# power_board1.net
KiCad netlist of a schematic drawn in Altium Designer
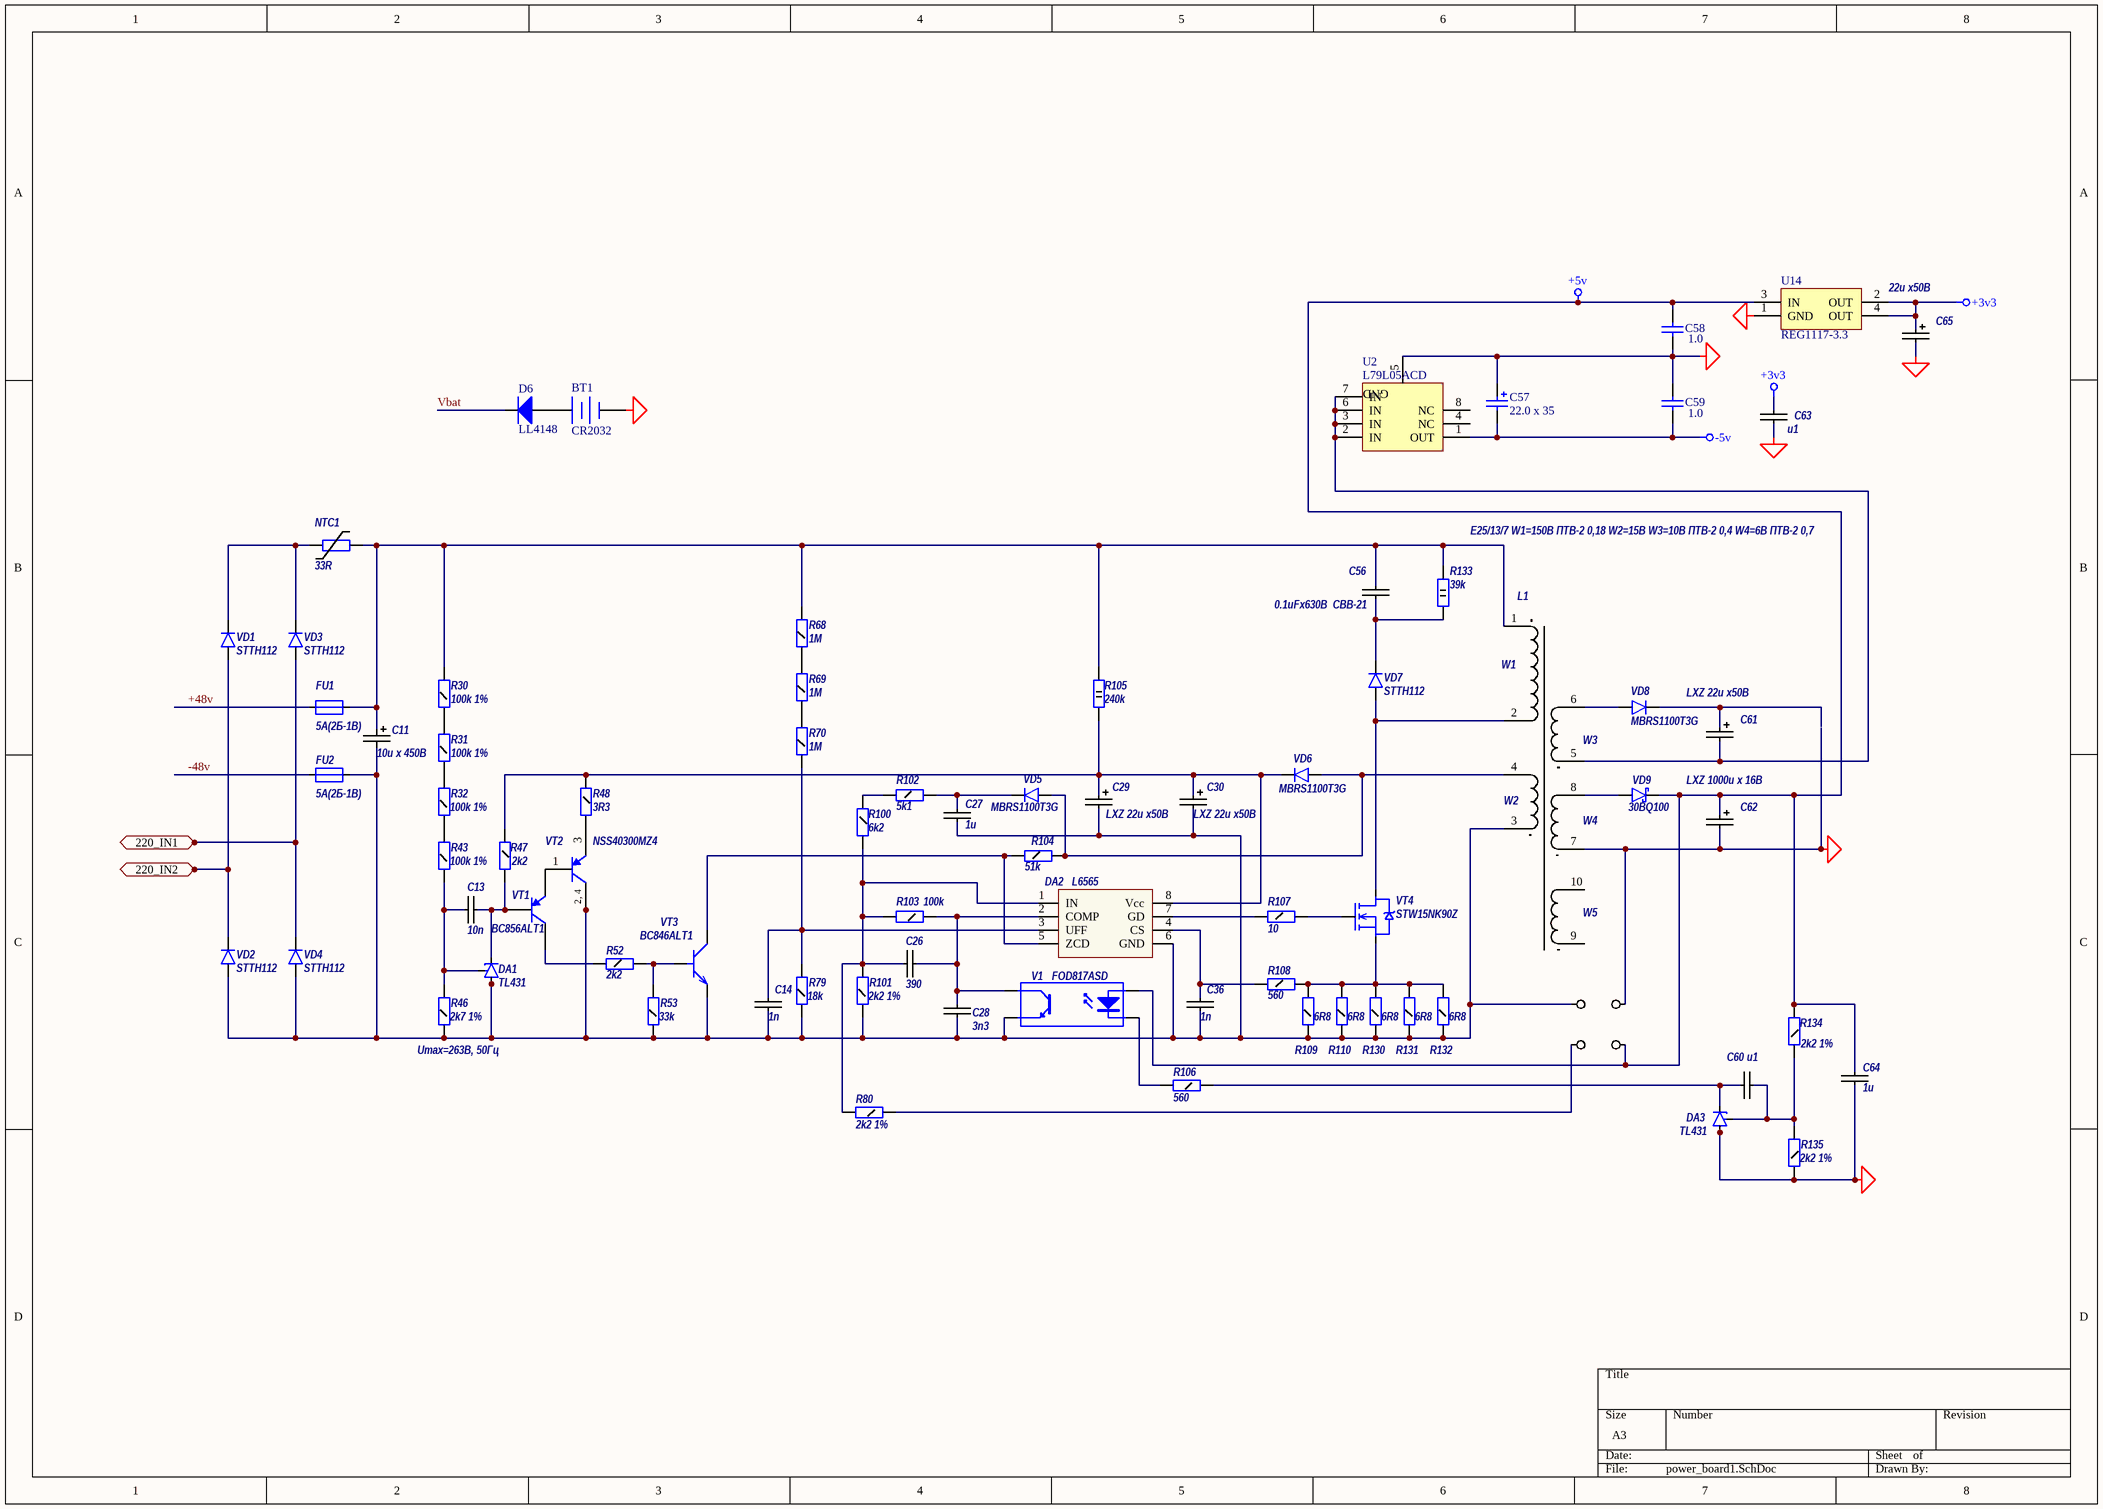
[diagram p0: power_board1.SchDoc]

(export (version "E")
  (design (tool "Eeschema 10.0.6"))
  (components
    (comp (ref "BT1")
      (value "CR2032")
      (footprint "BAT_SUPP")
      (description "Multicell Battery")
      (fields (field (name "MANUFACTURER") "Generic Components") (field (name "PUBLISHER") "Altium Limited"))
      (libsource (lib "Miscellaneous Devices") (part "Battery"))
    )
    (comp (ref "C11")
      (value "10u x 450B")
      (footprint "10uf x 450V")
      (fields (field (name "POWER") "450В"))
      (libsource (lib "Common") (part "10мкФ х 450В"))
    )
    (comp (ref "C13")
      (value "10n")
      (footprint "_1206")
      (fields
        (field (name "TOLERANCE") "10%")
        (field (name "MANUFACTURERPARTNUMBER") "CC1206 1мкФ±10% 50В X7R")
      )
      (libsource (lib "igorenja") (part "Capacitor"))
    )
    (comp (ref "C14")
      (value "1n")
      (footprint "_1206")
      (fields (field (name "TOLERANCE") "10%"))
      (libsource (lib "Common") (part "Capacitor"))
    )
    (comp (ref "C26")
      (value "390")
      (footprint "_1206")
      (fields (field (name "TOLERANCE") "10%"))
      (libsource (lib "Common") (part "Capacitor"))
    )
    (comp (ref "C27")
      (value "1u")
      (footprint "_1206")
      (fields (field (name "TOLERANCE") "10%"))
      (libsource (lib "Common") (part "Capacitor"))
    )
    (comp (ref "C28")
      (value "3n3")
      (footprint "_1206")
      (fields (field (name "TOLERANCE") "10%"))
      (libsource (lib "Common") (part "Capacitor"))
    )
    (comp (ref "C29")
      (value "LXZ 22u x50B")
      (footprint "CAP_POL_6.3x12")
      (fields (field (name "TOLERANCE") "20%") (field (name "MANUFACTURERPARTNUMBER") "22мкФ±20% 50В KMF"))
      (libsource (lib "igorenja") (part "CAP_POL"))
    )
    (comp (ref "C30")
      (value "LXZ 22u x50B")
      (footprint "CAP_POL_6.3x12")
      (fields (field (name "TOLERANCE") "20%") (field (name "MANUFACTURERPARTNUMBER") "22мкФ±20% 50В KMF"))
      (libsource (lib "igorenja") (part "CAP_POL"))
    )
    (comp (ref "C36")
      (value "1n")
      (footprint "_1206")
      (fields (field (name "TOLERANCE") "10%"))
      (libsource (lib "Common") (part "Capacitor"))
    )
    (comp (ref "C56")
      (value "0.1uFx630B  CBB-21")
      (footprint "0.1uf *630V")
      (fields (field (name "TOLERANCE") "20%") (field (name "MANUFACTURERPARTNUMBER") "0.1мкФ±20% 250В"))
      (libsource (lib "igorenja") (part "Capacitor"))
    )
    (comp (ref "C57")
      (value "22.0 x 35")
      (footprint "el3")
      (description "Polarized Capacitor (Radial)")
      (fields (field (name "MANUFACTURER") "Generic Components") (field (name "PUBLISHER") "Altium Limited"))
      (libsource (lib "PAL") (part "Cap Pol1"))
    )
    (comp (ref "C58")
      (value "1.0")
      (footprint "C3216-1206")
      (description "Capacitor (Semiconductor SIM Model)")
      (fields (field (name "MANUFACTURER") "Generic Components") (field (name "PUBLISHER") "Altium Limited"))
      (libsource (lib "Miscellaneous Devices") (part "Cap Semi"))
    )
    (comp (ref "C59")
      (value "1.0")
      (footprint "C3216-1206")
      (description "Capacitor (Semiconductor SIM Model)")
      (fields (field (name "MANUFACTURER") "Generic Components") (field (name "PUBLISHER") "Altium Limited"))
      (libsource (lib "Miscellaneous Devices") (part "Cap Semi"))
    )
    (comp (ref "C60")
      (value "u1")
      (footprint "_1206")
      (fields (field (name "TOLERANCE") "10%"))
      (libsource (lib "Common") (part "Capacitor"))
    )
    (comp (ref "C61")
      (value "LXZ 22u x50B")
      (footprint "CAP_POL_6.3x12")
      (fields (field (name "TOLERANCE") "20%") (field (name "MANUFACTURERPARTNUMBER") "22мкФ±20% 50В KMF"))
      (libsource (lib "igorenja") (part "CAP_POL"))
    )
    (comp (ref "C62")
      (value "LXZ 1000u x 16B")
      (footprint "CAP_POL_13x21")
      (description "1000 мкФ х 25В")
      (fields (field (name "TOLERANCE") "-20 +80%"))
      (libsource (lib "Common") (part "1000 мкФ х 25В"))
    )
    (comp (ref "C63")
      (value "u1")
      (footprint "_1206")
      (fields (field (name "TOLERANCE") "10%"))
      (libsource (lib "Common") (part "Capacitor"))
    )
    (comp (ref "C64")
      (value "1u")
      (footprint "_1206")
      (fields (field (name "TOLERANCE") "10%"))
      (libsource (lib "Common") (part "Capacitor"))
    )
    (comp (ref "C65")
      (value "22u x50B")
      (footprint "CAP_POL_6.3x12")
      (fields (field (name "TOLERANCE") "20%") (field (name "MANUFACTURERPARTNUMBER") "22мкФ±20% 50В KMF"))
      (libsource (lib "igorenja") (part "CAP_POL"))
    )
    (comp (ref "D6")
      (value "LL4148")
      (footprint "_1206d")
      (description "Default Diode")
      (fields (field (name "MANUFACTURER") "Generic Components") (field (name "PUBLISHER") "Altium Limited"))
      (libsource (lib "PAL") (part "Diode"))
    )
    (comp (ref "DA1") (value "TL431") (footprint "SO-G8") (libsource (lib "igorenja") (part "TL431")))
    (comp (ref "DA2") (value "L6565") (footprint "SO-G8") (libsource (lib "Common") (part "L6565")))
    (comp (ref "DA3") (value "TL431") (footprint "SO-G8") (libsource (lib "Common") (part "TL431")))
    (comp (ref "FU1") (value "5A(2Б-1В)") (footprint "FUSE-3A") (libsource (lib "igorenja") (part "FUSE")))
    (comp (ref "FU2") (value "5A(2Б-1В)") (footprint "FUSE-3A") (libsource (lib "igorenja") (part "FUSE")))
    (comp (ref "L1")
      (value "E25/13/7 W1=150B ПТВ-2 0,18 W2=15B W3=10B ПТВ-2 0,4 W4=6B ПТВ-2 0,7")
      (footprint "Lps_360RH")
      (description "Индуктивность")
      (libsource (lib "Common") (part "Lps_360RH"))
    )
    (comp (ref "NTC1")
      (value "33R")
      (footprint "NTC 33R")
      (description "Позистор")
      (libsource (lib "Common") (part "NTC 33R"))
    )
    (comp (ref "R30")
      (value "100k 1%")
      (footprint "_1206")
      (description "R1206")
      (fields (field (name "TOLERANCE") "5%"))
      (libsource (lib "") (part "R1206_1"))
    )
    (comp (ref "R31")
      (value "100k 1%")
      (footprint "_1206")
      (description "R1206")
      (fields (field (name "TOLERANCE") "5%"))
      (libsource (lib "") (part "R1206_1"))
    )
    (comp (ref "R32")
      (value "100k 1%")
      (footprint "_1206")
      (description "R1206")
      (fields (field (name "TOLERANCE") "1%"))
      (libsource (lib "") (part "R1206_1"))
    )
    (comp (ref "R43")
      (value "100k 1%")
      (footprint "_1206")
      (description "R1206")
      (fields (field (name "TOLERANCE") "1%"))
      (libsource (lib "") (part "R1206_1"))
    )
    (comp (ref "R46")
      (value "2k7 1%")
      (footprint "_1206")
      (description "R1206")
      (fields (field (name "TOLERANCE") "1%"))
      (libsource (lib "") (part "R1206_1"))
    )
    (comp (ref "R47")
      (value "2k2")
      (footprint "_1206")
      (description "R1206")
      (fields (field (name "TOLERANCE") "1%"))
      (libsource (lib "Common") (part "R1206"))
    )
    (comp (ref "R48")
      (value "3R3")
      (footprint "_1206")
      (description "R1206")
      (fields (field (name "TOLERANCE") "1%"))
      (libsource (lib "Common") (part "R1206"))
    )
    (comp (ref "R52")
      (value "2k2")
      (footprint "_1206")
      (description "R1206")
      (fields (field (name "TOLERANCE") "1%"))
      (libsource (lib "") (part "R1206_2"))
    )
    (comp (ref "R53")
      (value "33k")
      (footprint "_1206")
      (description "R1206")
      (fields (field (name "TOLERANCE") "1%"))
      (libsource (lib "") (part "R1206_1"))
    )
    (comp (ref "R68")
      (value "1M")
      (footprint "_1206")
      (description "R1206")
      (fields (field (name "TOLERANCE") "5%"))
      (libsource (lib "") (part "R1206_1"))
    )
    (comp (ref "R69")
      (value "1M")
      (footprint "_1206")
      (description "R1206")
      (fields (field (name "TOLERANCE") "5%"))
      (libsource (lib "") (part "R1206_1"))
    )
    (comp (ref "R70")
      (value "1M")
      (footprint "_1206")
      (description "R1206")
      (fields (field (name "TOLERANCE") "1%"))
      (libsource (lib "") (part "R1206_1"))
    )
    (comp (ref "R79")
      (value "18k")
      (footprint "_1206")
      (description "R1206")
      (fields (field (name "TOLERANCE") "1%"))
      (libsource (lib "") (part "R1206_1"))
    )
    (comp (ref "R80")
      (value "2k2 1%")
      (footprint "_1206")
      (description "R1206")
      (fields (field (name "TOLERANCE") "1%"))
      (libsource (lib "") (part "R1206_3"))
    )
    (comp (ref "R100")
      (value "6k2")
      (footprint "_1206")
      (description "R1206")
      (fields (field (name "TOLERANCE") "1%"))
      (libsource (lib "Common") (part "R1206"))
    )
    (comp (ref "R101")
      (value "2k2 1%")
      (footprint "_1206")
      (description "R1206")
      (fields (field (name "TOLERANCE") "1%"))
      (libsource (lib "") (part "R1206_1"))
    )
    (comp (ref "R102")
      (value "5k1")
      (footprint "_1206")
      (description "R1206")
      (fields (field (name "TOLERANCE") "1%"))
      (libsource (lib "") (part "R1206_2"))
    )
    (comp (ref "R103")
      (value "100k")
      (footprint "_1206")
      (description "R1206")
      (fields (field (name "TOLERANCE") "1%"))
      (libsource (lib "") (part "R1206_3"))
    )
    (comp (ref "R104")
      (value "51k")
      (footprint "_1206")
      (description "R1206")
      (fields (field (name "TOLERANCE") "5%"))
      (libsource (lib "") (part "R1206_2"))
    )
    (comp (ref "R105")
      (value "240k")
      (footprint "MF-2 vert")
      (fields (field (name "TOLERANCE") "10%"))
      (libsource (lib "Common") (part "Res 2W"))
    )
    (comp (ref "R106")
      (value "560")
      (footprint "_1206")
      (description "R1206")
      (fields (field (name "TOLERANCE") "1%"))
      (libsource (lib "") (part "R1206_3"))
    )
    (comp (ref "R107")
      (value "10")
      (footprint "_1206")
      (description "R1206")
      (fields (field (name "TOLERANCE") "5%"))
      (libsource (lib "") (part "R1206_2"))
    )
    (comp (ref "R108")
      (value "560")
      (footprint "_1206")
      (description "R1206")
      (fields (field (name "TOLERANCE") "5%"))
      (libsource (lib "") (part "R1206_2"))
    )
    (comp (ref "R109")
      (value "6R8")
      (footprint "_1206")
      (description "R1206")
      (fields (field (name "TOLERANCE") "5%"))
      (libsource (lib "") (part "R1206_1"))
    )
    (comp (ref "R110")
      (value "6R8")
      (footprint "_1206")
      (description "R1206")
      (fields (field (name "TOLERANCE") "5%"))
      (libsource (lib "") (part "R1206_1"))
    )
    (comp (ref "R130")
      (value "6R8")
      (footprint "_1206")
      (description "R1206")
      (fields (field (name "TOLERANCE") "5%"))
      (libsource (lib "") (part "R1206_1"))
    )
    (comp (ref "R131")
      (value "6R8")
      (footprint "_1206")
      (description "R1206")
      (fields (field (name "TOLERANCE") "5%"))
      (libsource (lib "") (part "R1206_1"))
    )
    (comp (ref "R132")
      (value "6R8")
      (footprint "_1206")
      (description "R1206")
      (fields (field (name "TOLERANCE") "5%"))
      (libsource (lib "") (part "R1206_1"))
    )
    (comp (ref "R133") (value "39k") (footprint "Res 2W") (libsource (lib "Common") (part "Res 2W")))
    (comp (ref "R134")
      (value "2k2 1%")
      (footprint "_1206")
      (description "R1206")
      (fields (field (name "TOLERANCE") "1%"))
      (libsource (lib "") (part "R1206_2"))
    )
    (comp (ref "R135")
      (value "2k2 1%")
      (footprint "_1206")
      (description "R1206")
      (fields (field (name "TOLERANCE") "1%"))
      (libsource (lib "") (part "R1206_2"))
    )
    (comp (ref "U2")
      (value "L79L05ACD")
      (footprint "SO-G8")
      (description "Negative Voltage Regulator")
      (fields (field (name "MANUFACTURER") "ST-Microelectronics") (field (name "PUBLISHER") "Altium Limited"))
      (libsource (lib "ST Power Mgt Voltage Regulator") (part "L79L05ACD"))
    )
    (comp (ref "U14")
      (value "REG1117-3.3")
      (footprint "SIP-G3/C7.4")
      (description "800mA and 1A Low Dropout Positive Regulator 2.85V, 3.3V, 5V, and Adjustable")
      (fields (field (name "MANUFACTURER") "Burr-Brown") (field (name "PUBLISHER") "Altium Limited"))
      (libsource (lib "BB Power Mgt Voltage Regulator") (part "REG1117-3.3"))
    )
    (comp (ref "V1")
      (value "FOD817ASD")
      (footprint "FOD817ASD")
      (libsource (lib "Common") (part "FOD817ASD"))
    )
    (comp (ref "VD1")
      (value "STTH112")
      (footprint "10bq*")
      (fields (field (name "MANUFACTURERPARTNUMBER") "STTH2R060U"))
      (libsource (lib "IVERTORSICH") (part "DIOD_2"))
    )
    (comp (ref "VD2")
      (value "STTH112")
      (footprint "10bq*")
      (fields (field (name "MANUFACTURERPARTNUMBER") "STTH2R060U"))
      (libsource (lib "IVERTORSICH") (part "DIOD_2"))
    )
    (comp (ref "VD3")
      (value "STTH112")
      (footprint "10bq*")
      (fields (field (name "MANUFACTURERPARTNUMBER") "STTH2R060U"))
      (libsource (lib "IVERTORSICH") (part "DIOD_2"))
    )
    (comp (ref "VD4")
      (value "STTH112")
      (footprint "10bq*")
      (fields (field (name "MANUFACTURERPARTNUMBER") "STTH2R060U"))
      (libsource (lib "IVERTORSICH") (part "DIOD_2"))
    )
    (comp (ref "VD5") (value "MBRS1100T3G") (footprint "10bq*") (libsource (lib "Common") (part "DIOD_1")))
    (comp (ref "VD6") (value "MBRS1100T3G") (footprint "10bq*") (libsource (lib "Common") (part "DIOD_1")))
    (comp (ref "VD7")
      (value "STTH112")
      (footprint "10bq*")
      (fields (field (name "MANUFACTURERPARTNUMBER") "STTH2R060U"))
      (libsource (lib "IVERTORSICH") (part "DIOD_2"))
    )
    (comp (ref "VD8") (value "MBRS1100T3G") (footprint "10bq*") (libsource (lib "Common") (part "DIOD_1")))
    (comp (ref "VD9") (value "30BQ100") (footprint "30bq*") (libsource (lib "igorenja") (part "DIOD_SH")))
    (comp (ref "VT1")
      (value "BC856ALT1")
      (footprint "318-08")
      (description "General Purpose Transistor PNP Silicon")
      (fields (field (name "MANUFACTURER") "ON Semiconductor") (field (name "PUBLISHER") "Altium Limited"))
      (libsource (lib "Common") (part "BC856ALT1"))
    )
    (comp (ref "VT2")
      (value "NSS40300MZ4")
      (footprint "SOT223_N")
      (description "Транзистор")
      (fields (field (name "PUBLISHER") "Altium Limited"))
      (libsource (lib "Philips Discrete BJT - Medium Power") (part "BSP32"))
    )
    (comp (ref "VT3")
      (value "BC846ALT1")
      (footprint "SOT-23")
      (libsource (lib "igorenja") (part "TRANS_npn"))
    )
    (comp (ref "VT4")
      (value "STW15NK90Z")
      (footprint "IRFP4468_BS")
      (fields (field (name "MANUFACTURER") "International Rectifier"))
      (libsource (lib "Common") (part "irfp4468_otv"))
    )
    (comp (ref "XP1") (value "PAD") (footprint "PAD_otv") (libsource (lib "Common") (part "PAD")))
    (comp (ref "XP2") (value "PAD") (footprint "PAD_otv") (libsource (lib "Common") (part "PAD")))
    (comp (ref "XP3") (value "PAD") (footprint "PAD_otv") (libsource (lib "Common") (part "PAD")))
    (comp (ref "XP4") (value "PAD") (footprint "PAD_otv") (libsource (lib "Common") (part "PAD")))
    (comp (ref "XP5") (value "PAD") (footprint "PAD_otv") (libsource (lib "Common") (part "PAD")))
    (comp (ref "XP6") (value "PAD") (footprint "PAD_otv") (libsource (lib "Common") (part "PAD")))
  )
  (nets
    (net (code "1") (name "+3v3") (class "Default")
      (node (ref "C63") (pin "1") (pinfunction "OA_1") (pintype "passive"))
      (node (ref "C65") (pin "+") (pintype "passive"))
      (node (ref "U14") (pin "2") (pinfunction "OUT_2") (pintype "power_in"))
      (node (ref "U14") (pin "4") (pinfunction "OUT_4") (pintype "power_in"))
    )
    (net (code "2") (name "+5v") (class "Default")
      (node (ref "C58") (pin "2") (pinfunction "2_2") (pintype "passive"))
      (node (ref "C62") (pin "+") (pintype "passive"))
      (node (ref "C64") (pin "1") (pinfunction "OA_1") (pintype "passive"))
      (node (ref "R134") (pin "2") (pinfunction "2_2") (pintype "passive"))
      (node (ref "U14") (pin "3") (pinfunction "IN_3") (pintype "power_in"))
      (node (ref "V1") (pin "1") (pinfunction "A_1") (pintype "passive"))
      (node (ref "VD9") (pin "2") (pintype "passive"))
      (node (ref "XP6") (pin "1") (pintype "passive"))
    )
    (net (code "3") (name "-5v") (class "Default")
      (node (ref "C57") (pin "2") (pinfunction "2_2") (pintype "passive"))
      (node (ref "C59") (pin "1") (pinfunction "1_1") (pintype "passive"))
      (node (ref "U2") (pin "1") (pinfunction "OUT_1") (pintype "power_in"))
    )
    (net (code "4") (name "/+48v") (class "Default")
      (node (ref "FU1") (pin "1") (pinfunction "0_1") (pintype "passive"))
    )
    (net (code "5") (name "/-48v") (class "Default")
      (node (ref "FU2") (pin "1") (pinfunction "0_1") (pintype "passive"))
    )
    (net (code "6") (name "/220_IN1") (class "Default")
      (node (ref "VD3") (pin "1") (pintype "passive"))
      (node (ref "VD4") (pin "2") (pintype "passive"))
      (node (ref "XP1") (pin "1") (pintype "passive"))
    )
    (net (code "7") (name "/220_IN2") (class "Default")
      (node (ref "VD1") (pin "1") (pintype "passive"))
      (node (ref "VD2") (pin "2") (pintype "passive"))
      (node (ref "XP2") (pin "1") (pintype "passive"))
    )
    (net (code "8") (name "/Vbat") (class "Default")
      (node (ref "D6") (pin "2") (pinfunction "K_2") (pintype "passive"))
    )
    (net (code "9") (name "GND") (class "Default")
      (node (ref "BT1") (pin "2") (pinfunction "-_2") (pintype "passive"))
      (node (ref "C57") (pin "1") (pinfunction "1_1") (pintype "passive"))
      (node (ref "C58") (pin "1") (pinfunction "1_1") (pintype "passive"))
      (node (ref "C59") (pin "2") (pinfunction "2_2") (pintype "passive"))
      (node (ref "C62") (pin "-") (pintype "passive"))
      (node (ref "C63") (pin "2") (pinfunction "OA_2") (pintype "passive"))
      (node (ref "C64") (pin "2") (pinfunction "OA_2") (pintype "passive"))
      (node (ref "C65") (pin "-") (pintype "passive"))
      (node (ref "DA3") (pin "6") (pintype "passive"))
      (node (ref "DA3") (pin "7") (pintype "passive"))
      (node (ref "L1") (pin "7") (pintype "passive"))
      (node (ref "R135") (pin "1") (pinfunction "1_1") (pintype "passive"))
      (node (ref "U14") (pin "1") (pinfunction "GND_1") (pintype "power_in"))
      (node (ref "U2") (pin "5") (pinfunction "GND_5") (pintype "power_in"))
      (node (ref "XP5") (pin "1") (pintype "passive"))
    )
    (net (code "10") (name "Net-(BT1-+)") (class "Default")
      (node (ref "BT1") (pin "1") (pinfunction "+_1") (pintype "passive"))
      (node (ref "D6") (pin "1") (pinfunction "A_1") (pintype "passive"))
    )
    (net (code "11") (name "Net-(C13-OA-Pad1)") (class "Default")
      (node (ref "C13") (pin "1") (pinfunction "OA_1") (pintype "passive"))
      (node (ref "DA1") (pin "8") (pintype "passive"))
      (node (ref "R43") (pin "1") (pinfunction "1_1") (pintype "passive"))
      (node (ref "R46") (pin "2") (pinfunction "2_2") (pintype "passive"))
    )
    (net (code "12") (name "Net-(C27-OA-Pad1)") (class "Default")
      (node (ref "C27") (pin "1") (pinfunction "OA_1") (pintype "passive"))
      (node (ref "R102") (pin "2") (pinfunction "2_2") (pintype "passive"))
      (node (ref "VD5") (pin "2") (pintype "passive"))
    )
    (net (code "13") (name "Net-(C56-OA-Pad2)") (class "Default")
      (node (ref "C56") (pin "2") (pinfunction "OA_2") (pintype "passive"))
      (node (ref "R133") (pin "1") (pinfunction "1_1") (pintype "passive"))
      (node (ref "VD7") (pin "2") (pintype "passive"))
    )
    (net (code "14") (name "Net-(C60-OA-Pad1)") (class "Default")
      (node (ref "C60") (pin "1") (pinfunction "OA_1") (pintype "passive"))
      (node (ref "DA3") (pin "1") (pintype "passive"))
      (node (ref "R106") (pin "1") (pinfunction "1_1") (pintype "passive"))
    )
    (net (code "15") (name "Net-(C60-OA-Pad2)") (class "Default")
      (node (ref "C60") (pin "2") (pinfunction "OA_2") (pintype "passive"))
      (node (ref "DA3") (pin "8") (pintype "passive"))
      (node (ref "R134") (pin "1") (pinfunction "1_1") (pintype "passive"))
      (node (ref "R135") (pin "2") (pinfunction "2_2") (pintype "passive"))
    )
    (net (code "16") (name "Net-(C61-Pad+)") (class "Default")
      (node (ref "C61") (pin "+") (pintype "passive"))
      (node (ref "VD8") (pin "2") (pintype "passive"))
    )
    (net (code "17") (name "Net-(C61-Pad-)") (class "Default")
      (node (ref "C61") (pin "-") (pintype "passive"))
      (node (ref "L1") (pin "5") (pintype "passive"))
      (node (ref "U2") (pin "2") (pinfunction "IN_2") (pintype "power_in"))
      (node (ref "U2") (pin "3") (pinfunction "IN_3") (pintype "power_in"))
      (node (ref "U2") (pin "6") (pinfunction "IN_6") (pintype "power_in"))
      (node (ref "U2") (pin "7") (pinfunction "IN_7") (pintype "power_in"))
    )
    (net (code "18") (name "Net-(DA2-COMP)") (class "Default")
      (node (ref "C26") (pin "2") (pinfunction "OA_2") (pintype "passive"))
      (node (ref "C28") (pin "2") (pinfunction "OA_2") (pintype "passive"))
      (node (ref "DA2") (pin "2") (pinfunction "COMP_2") (pintype "passive"))
      (node (ref "R103") (pin "1") (pinfunction "1_1") (pintype "passive"))
      (node (ref "V1") (pin "4") (pinfunction "C_4") (pintype "passive"))
    )
    (net (code "19") (name "Net-(DA2-CS)") (class "Default")
      (node (ref "C36") (pin "1") (pinfunction "OA_1") (pintype "passive"))
      (node (ref "DA2") (pin "4") (pinfunction "CS_4") (pintype "passive"))
      (node (ref "R108") (pin "1") (pinfunction "1_1") (pintype "passive"))
    )
    (net (code "20") (name "Net-(DA2-GD)") (class "Default")
      (node (ref "DA2") (pin "7") (pinfunction "GD_7") (pintype "passive"))
      (node (ref "R107") (pin "1") (pinfunction "1_1") (pintype "passive"))
    )
    (net (code "21") (name "Net-(DA2-GND)") (class "Default")
      (node (ref "C11") (pin "2") (pintype "passive"))
      (node (ref "C14") (pin "2") (pinfunction "OA_2") (pintype "passive"))
      (node (ref "C27") (pin "2") (pinfunction "OA_2") (pintype "passive"))
      (node (ref "C28") (pin "1") (pinfunction "OA_1") (pintype "passive"))
      (node (ref "C29") (pin "-") (pintype "passive"))
      (node (ref "C30") (pin "-") (pintype "passive"))
      (node (ref "C36") (pin "2") (pinfunction "OA_2") (pintype "passive"))
      (node (ref "DA1") (pin "6") (pintype "passive"))
      (node (ref "DA1") (pin "7") (pintype "passive"))
      (node (ref "DA2") (pin "6") (pinfunction "GND_6") (pintype "passive"))
      (node (ref "FU2") (pin "2") (pinfunction "1_2") (pintype "passive"))
      (node (ref "L1") (pin "3") (pintype "passive"))
      (node (ref "R101") (pin "1") (pinfunction "1_1") (pintype "passive"))
      (node (ref "R109") (pin "1") (pinfunction "1_1") (pintype "passive"))
      (node (ref "R110") (pin "1") (pinfunction "1_1") (pintype "passive"))
      (node (ref "R130") (pin "1") (pinfunction "1_1") (pintype "passive"))
      (node (ref "R131") (pin "1") (pinfunction "1_1") (pintype "passive"))
      (node (ref "R132") (pin "1") (pinfunction "1_1") (pintype "passive"))
      (node (ref "R46") (pin "1") (pinfunction "1_1") (pintype "passive"))
      (node (ref "R53") (pin "1") (pinfunction "1_1") (pintype "passive"))
      (node (ref "R79") (pin "1") (pinfunction "1_1") (pintype "passive"))
      (node (ref "V1") (pin "3") (pinfunction "E_3") (pintype "passive"))
      (node (ref "VD2") (pin "1") (pintype "passive"))
      (node (ref "VD4") (pin "1") (pintype "passive"))
      (node (ref "VT2") (pin "2") (pinfunction "C_2") (pintype "passive"))
      (node (ref "VT2") (pin "4") (pinfunction "C_4") (pintype "passive"))
      (node (ref "VT3") (pin "2") (pintype "passive"))
      (node (ref "XP3") (pin "1") (pintype "passive"))
    )
    (net (code "22") (name "Net-(DA2-IN)") (class "Default")
      (node (ref "C26") (pin "1") (pinfunction "OA_1") (pintype "passive"))
      (node (ref "DA2") (pin "1") (pinfunction "IN_1") (pintype "passive"))
      (node (ref "R100") (pin "2") (pinfunction "2_2") (pintype "passive"))
      (node (ref "R101") (pin "2") (pinfunction "2_2") (pintype "passive"))
      (node (ref "R103") (pin "2") (pinfunction "2_2") (pintype "passive"))
      (node (ref "R80") (pin "2") (pinfunction "2_2") (pintype "passive"))
    )
    (net (code "23") (name "Net-(DA2-UFF)") (class "Default")
      (node (ref "C14") (pin "1") (pinfunction "OA_1") (pintype "passive"))
      (node (ref "DA2") (pin "3") (pinfunction "UFF_3") (pintype "passive"))
      (node (ref "R70") (pin "1") (pinfunction "1_1") (pintype "passive"))
      (node (ref "R79") (pin "2") (pinfunction "2_2") (pintype "passive"))
    )
    (net (code "24") (name "Net-(DA2-Vcc)") (class "Default")
      (node (ref "C29") (pin "+") (pintype "passive"))
      (node (ref "C30") (pin "+") (pintype "passive"))
      (node (ref "DA2") (pin "8") (pinfunction "Vcc_8") (pintype "passive"))
      (node (ref "R105") (pin "1") (pinfunction "1_1") (pintype "passive"))
      (node (ref "R47") (pin "1") (pinfunction "1_1") (pintype "passive"))
      (node (ref "R48") (pin "1") (pinfunction "1_1") (pintype "passive"))
      (node (ref "VD6") (pin "2") (pintype "passive"))
    )
    (net (code "25") (name "Net-(DA2-ZCD)") (class "Default")
      (node (ref "DA2") (pin "5") (pinfunction "ZCD_5") (pintype "passive"))
      (node (ref "R104") (pin "1") (pinfunction "1_1") (pintype "passive"))
      (node (ref "VT3") (pin "3") (pintype "passive"))
    )
    (net (code "26") (name "Net-(FU1-1)") (class "Default")
      (node (ref "C11") (pin "1") (pintype "passive"))
      (node (ref "C56") (pin "1") (pinfunction "OA_1") (pintype "passive"))
      (node (ref "FU1") (pin "2") (pinfunction "1_2") (pintype "passive"))
      (node (ref "L1") (pin "1") (pintype "passive"))
      (node (ref "NTC1") (pin "2") (pinfunction "2_2") (pintype "passive"))
      (node (ref "R105") (pin "2") (pinfunction "2_2") (pintype "passive"))
      (node (ref "R133") (pin "2") (pinfunction "2_2") (pintype "passive"))
      (node (ref "R30") (pin "2") (pinfunction "2_2") (pintype "passive"))
      (node (ref "R68") (pin "2") (pinfunction "2_2") (pintype "passive"))
    )
    (net (code "27") (name "Net-(L1-Pad4)") (class "Default")
      (node (ref "L1") (pin "4") (pintype "passive"))
      (node (ref "R104") (pin "2") (pinfunction "2_2") (pintype "passive"))
      (node (ref "VD5") (pin "1") (pintype "passive"))
      (node (ref "VD6") (pin "1") (pintype "passive"))
    )
    (net (code "28") (name "Net-(L1-Pad6)") (class "Default")
      (node (ref "L1") (pin "6") (pintype "passive"))
      (node (ref "VD8") (pin "1") (pintype "passive"))
    )
    (net (code "29") (name "Net-(L1-Pad8)") (class "Default")
      (node (ref "L1") (pin "8") (pintype "passive"))
      (node (ref "VD9") (pin "1") (pintype "passive"))
    )
    (net (code "30") (name "Net-(NTC1-Pad1)") (class "Default")
      (node (ref "NTC1") (pin "1") (pinfunction "1_1") (pintype "passive"))
      (node (ref "VD1") (pin "2") (pintype "passive"))
      (node (ref "VD3") (pin "2") (pintype "passive"))
    )
    (net (code "31") (name "Net-(R30-Pad1)") (class "Default")
      (node (ref "R30") (pin "1") (pinfunction "1_1") (pintype "passive"))
      (node (ref "R31") (pin "2") (pinfunction "2_2") (pintype "passive"))
    )
    (net (code "32") (name "Net-(R31-Pad1)") (class "Default")
      (node (ref "R31") (pin "1") (pinfunction "1_1") (pintype "passive"))
      (node (ref "R32") (pin "2") (pinfunction "2_2") (pintype "passive"))
    )
    (net (code "33") (name "Net-(R32-Pad1)") (class "Default")
      (node (ref "R32") (pin "1") (pinfunction "1_1") (pintype "passive"))
      (node (ref "R43") (pin "2") (pinfunction "2_2") (pintype "passive"))
    )
    (net (code "34") (name "Net-(R52-Pad2)") (class "Default")
      (node (ref "R52") (pin "2") (pinfunction "2_2") (pintype "passive"))
      (node (ref "R53") (pin "2") (pinfunction "2_2") (pintype "passive"))
      (node (ref "VT3") (pin "1") (pintype "passive"))
    )
    (net (code "35") (name "Net-(R68-Pad1)") (class "Default")
      (node (ref "R68") (pin "1") (pinfunction "1_1") (pintype "passive"))
      (node (ref "R69") (pin "2") (pinfunction "2_2") (pintype "passive"))
    )
    (net (code "36") (name "Net-(R69-Pad1)") (class "Default")
      (node (ref "R69") (pin "1") (pinfunction "1_1") (pintype "passive"))
      (node (ref "R70") (pin "2") (pinfunction "2_2") (pintype "passive"))
    )
    (net (code "37") (name "Net-(R80-Pad1)") (class "Default")
      (node (ref "R80") (pin "1") (pinfunction "1_1") (pintype "passive"))
      (node (ref "XP4") (pin "1") (pintype "passive"))
    )
    (net (code "38") (name "Net-(R100-Pad1)") (class "Default")
      (node (ref "R100") (pin "1") (pinfunction "1_1") (pintype "passive"))
      (node (ref "R102") (pin "1") (pinfunction "1_1") (pintype "passive"))
    )
    (net (code "39") (name "Net-(V1-K)") (class "Default")
      (node (ref "R106") (pin "2") (pinfunction "2_2") (pintype "passive"))
      (node (ref "V1") (pin "2") (pinfunction "K_2") (pintype "passive"))
    )
    (net (code "40") (name "Net-(VT1-B)") (class "Default")
      (node (ref "C13") (pin "2") (pinfunction "OA_2") (pintype "passive"))
      (node (ref "DA1") (pin "1") (pintype "passive"))
      (node (ref "R47") (pin "2") (pinfunction "2_2") (pintype "passive"))
      (node (ref "VT1") (pin "1") (pinfunction "B_1") (pintype "passive"))
    )
    (net (code "41") (name "Net-(VT1-C)") (class "Default")
      (node (ref "R52") (pin "1") (pinfunction "1_1") (pintype "passive"))
      (node (ref "VT1") (pin "3") (pinfunction "C_3") (pintype "passive"))
    )
    (net (code "42") (name "Net-(VT1-E)") (class "Default")
      (node (ref "VT1") (pin "2") (pinfunction "E_2") (pintype "passive"))
      (node (ref "VT2") (pin "1") (pinfunction "B_1") (pintype "passive"))
    )
    (net (code "43") (name "Net-(VT2-E)") (class "Default")
      (node (ref "R48") (pin "2") (pinfunction "2_2") (pintype "passive"))
      (node (ref "VT2") (pin "3") (pinfunction "E_3") (pintype "passive"))
    )
    (net (code "44") (name "Net-(VT4-drane)") (class "Default")
      (node (ref "L1") (pin "2") (pintype "passive"))
      (node (ref "VD7") (pin "1") (pintype "passive"))
      (node (ref "VT4") (pin "2") (pinfunction "drane_2") (pintype "passive"))
    )
    (net (code "45") (name "Net-(VT4-gate)") (class "Default")
      (node (ref "R107") (pin "2") (pinfunction "2_2") (pintype "passive"))
      (node (ref "VT4") (pin "1") (pinfunction "gate_1") (pintype "passive"))
    )
    (net (code "46") (name "Net-(VT4-sourse)") (class "Default")
      (node (ref "R108") (pin "2") (pinfunction "2_2") (pintype "passive"))
      (node (ref "R109") (pin "2") (pinfunction "2_2") (pintype "passive"))
      (node (ref "R110") (pin "2") (pinfunction "2_2") (pintype "passive"))
      (node (ref "R130") (pin "2") (pinfunction "2_2") (pintype "passive"))
      (node (ref "R131") (pin "2") (pinfunction "2_2") (pintype "passive"))
      (node (ref "R132") (pin "2") (pinfunction "2_2") (pintype "passive"))
      (node (ref "VT4") (pin "3") (pinfunction "sourse_3") (pintype "passive"))
    )
    (net (code "47") (name "unconnected-(L1-Pad9)") (class "Default")
      (node (ref "L1") (pin "9") (pintype "passive"))
    )
    (net (code "48") (name "unconnected-(L1-Pad10)") (class "Default")
      (node (ref "L1") (pin "10") (pintype "passive"))
    )
    (net (code "49") (name "unconnected-(U2-NC-Pad4)") (class "Default")
      (node (ref "U2") (pin "4") (pinfunction "NC_4") (pintype "passive"))
    )
    (net (code "50") (name "unconnected-(U2-NC-Pad8)") (class "Default")
      (node (ref "U2") (pin "8") (pinfunction "NC_8") (pintype "passive"))
    )
  )
)
